# Voltage_60_Measure.net
KiCad netlist of a schematic drawn in Altium Designer
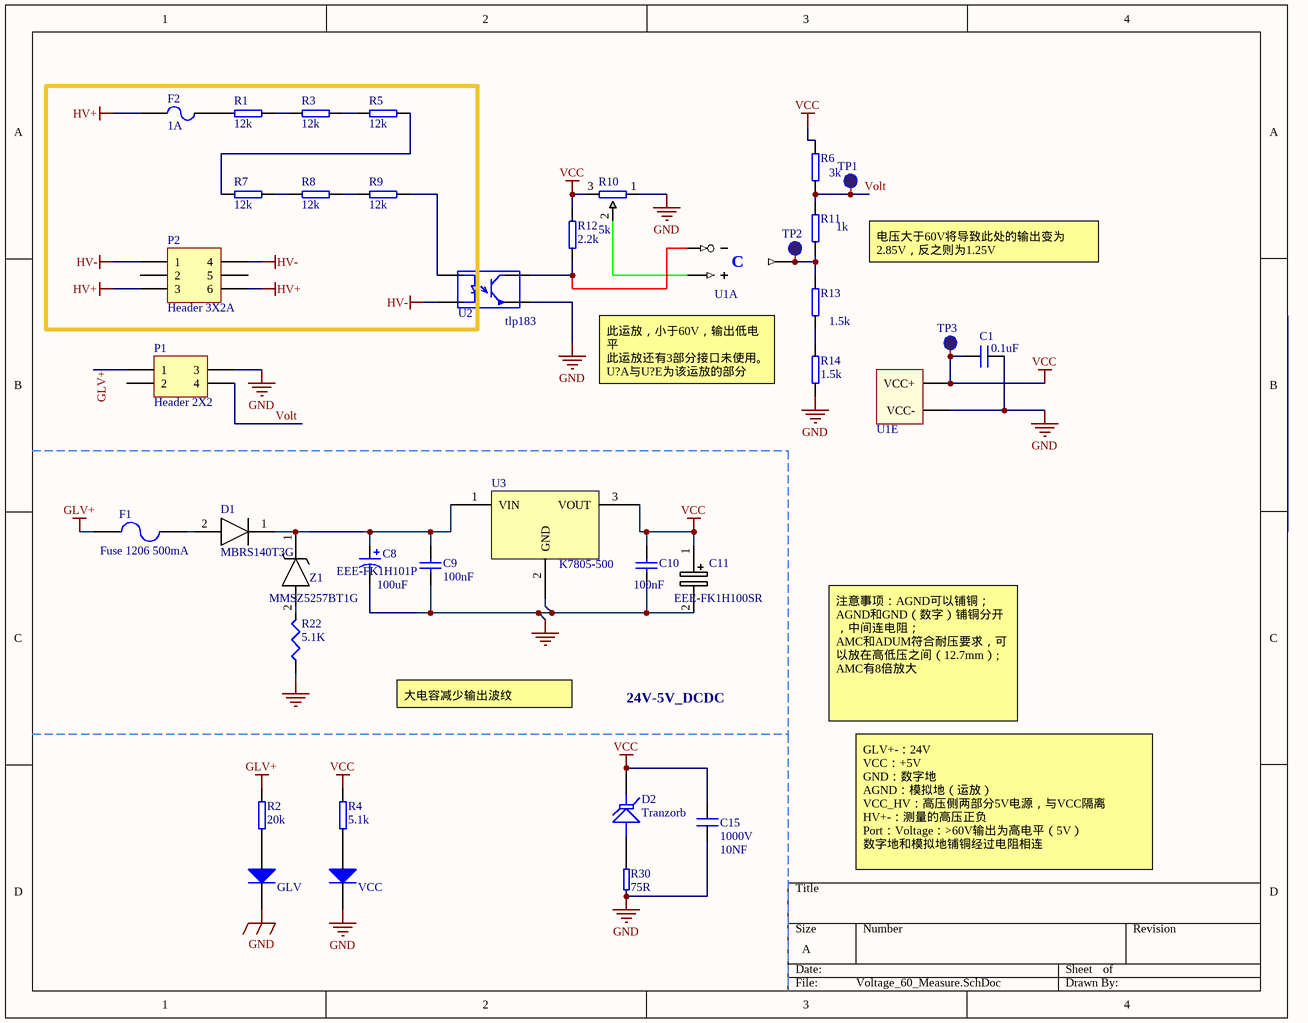
[diagram p0: Voltage_60_Measure.SchDoc]

(export (version "E")
  (design (tool "Eeschema 10.0.6"))
  (components
    (comp (ref "C1")
      (value "0.1uF")
      (footprint "C0603")
      (description "多层陶瓷电容器MLCC - SMD/SMT 0603 .1uF 50volts X7R 10%")
      (fields (field (name "MANUFACTURER") "Vishay") (field (name "VOLTAGE") "50V"))
      (libsource (lib "TSAL") (part "VJ0603Y104KXAAC"))
    )
    (comp (ref "C8")
      (value "EEE-FK1H101P")
      (footprint "C-RB-SD8")
      (description "Polarized Capacitor (Radial)")
      (fields (field (name "ALTIUM_VALUE") "100uF") (field (name "PUBLISHER") "Altium Limited"))
      (libsource (lib "Miscellaneous Devices") (part "Cap Pol1"))
    )
    (comp (ref "C9")
      (value "100nF")
      (footprint "C1206")
      (description "Capacitor (Semiconductor SIM Model)")
      (fields (field (name "Comment") "Cap Semi") (field (name "PUBLISHER") "Altium Limited"))
      (libsource (lib "Miscellaneous Devices") (part "Cap Semi"))
    )
    (comp (ref "C10")
      (value "100nF")
      (footprint "C1206")
      (description "Capacitor (Semiconductor SIM Model)")
      (fields (field (name "Comment") "Cap Semi") (field (name "PUBLISHER") "Altium Limited"))
      (libsource (lib "Miscellaneous Devices") (part "Cap Semi"))
    )
    (comp (ref "C11")
      (value "EEE-FK1H100SR")
      (footprint "CAPAE430X610N")
      (description "Capacitor Polarised")
      (fields (field (name "MOUSER PART NUMBER") "667-EEE-FK1H100SR"))
      (libsource (lib "*") (part "EEE-FK1H100SR"))
    )
    (comp (ref "C15")
      (value "10NF")
      (footprint "C1206")
      (description "多层陶瓷电容器MLCC - SMD/SMT 1206 1000pF 1KV C0G 5%")
      (fields
        (field (name "MANUFACTURER") "Vishay")
        (field (name "VOLTAGE") "1000V")
        (field (name "Comment") "VJ1206A102JXGAT5Z")
      )
      (libsource (lib "controller") (part "VJ1206A102JXGAT5Z"))
    )
    (comp (ref "D1")
      (value "MBRS140T3G")
      (footprint "DIOM5436X247N")
      (description "Diode")
      (fields (field (name "MOUSER PART NUMBER") "863-MBRS140T3G") (field (name "RS PART NUMBER") "5452074P"))
      (libsource (lib "*") (part "MBRS140T3G"))
    )
    (comp (ref "D2")
      (value "Tranzorb")
      (footprint "SOD123")
      (description "Transient Voltage Suppression (TVS) Diode")
      (fields (field (name "PUBLISHER") "Altium Limited"))
      (libsource (lib "Miscellaneous Devices") (part "Tranzorb"))
    )
    (comp (ref "F1")
      (value "Fuse 1206 500mA")
      (footprint "1206")
      (description "littelfuse 0437 .500")
      (fields (field (name "PUBLISHER") "Altium Limited"))
      (libsource (lib "Miscellaneous Devices") (part "Fuse 2"))
    )
    (comp (ref "F2")
      (value "1A")
      (footprint "0485500DR")
      (description "Fast-Acting 485 Series")
      (fields (field (name "MANUFACTURER") "Littefuse") (field (name "Comment") "0485500.DR"))
      (libsource (lib "TSAL") (part "0485500.DR"))
    )
    (comp (ref "GLV")
      (value "VLMB1310-GS08")
      (footprint "BlueLED 0603")
      (description "标准LED-SMD Blue Clear Non-Diff")
      (fields (field (name "MANUFACTURER") "Vishay"))
      (libsource (lib "BMU2019") (part "VLMB1310-GS08"))
    )
    (comp (ref "P1")
      (value "Header 2X2")
      (footprint "PHB2*2")
      (description "Header, 2-Pin, Dual row")
      (fields (field (name "PUBLISHER") "Altium Limited"))
      (libsource (lib "Miscellaneous Connectors") (part "Header 2X2"))
    )
    (comp (ref "P2")
      (value "Header 3X2A")
      (footprint "43045-0612")
      (description "Header, 3-Pin, Dual row")
      (fields (field (name "PUBLISHER") "Altium Limited"))
      (libsource (lib "Miscellaneous Connectors") (part "Header 3X2A"))
    )
    (comp (ref "R1")
      (value "12k")
      (footprint "R2512")
      (description "Thin Film Resistors - SMD 2.5watt 2Kohms .1% 25 PPM")
      (fields (field (name "MANUFACTURER") "Vishay") (field (name "VOLTAGE") "200V"))
      (libsource (lib "TSAL") (part "PHP02512E2001BST5"))
    )
    (comp (ref "R2")
      (value "20k")
      (footprint "R0603")
      (description "Thick Film Resistors - SMD 1/10Watt 20Kohms 1% Commercial Use")
      (fields (field (name "MANUFACTURER") "Vishay") (field (name "VOLTAGE") "75V"))
      (libsource (lib "BMU2019") (part "CRCW060320K0FKEAC"))
    )
    (comp (ref "R3")
      (value "12k")
      (footprint "R2512")
      (description "Thin Film Resistors - SMD 2.5watt 2Kohms .1% 25 PPM")
      (fields (field (name "MANUFACTURER") "Vishay") (field (name "VOLTAGE") "200V"))
      (libsource (lib "TSAL") (part "PHP02512E2001BST5"))
    )
    (comp (ref "R4")
      (value "5.1k")
      (footprint "R0603")
      (description "Thick Film Resistors - SMD 1/10Watt 5.1Kohms 1% Commercial Use")
      (fields (field (name "MANUFACTURER") "Vishay") (field (name "Comment") "CRCW06035K10JNEAC"))
      (libsource (lib "BMU2019") (part "CRCW06035K10JNEAC"))
    )
    (comp (ref "R5")
      (value "12k")
      (footprint "R2512")
      (description "Thin Film Resistors - SMD 2.5watt 2Kohms .1% 25 PPM")
      (fields (field (name "MANUFACTURER") "Vishay") (field (name "VOLTAGE") "200V"))
      (libsource (lib "TSAL") (part "PHP02512E2001BST5"))
    )
    (comp (ref "R6")
      (value "3k")
      (footprint "R0603")
      (description "Thick Film Resistors - SMD 1/10Watt 1.5Kohms 1% Commercial Use")
      (fields (field (name "MANUFACTURER") "Vishay") (field (name "Comment") "CRCW06031K50FKEAC"))
      (libsource (lib "BMU2019") (part "CRCW06031K50FKEAC"))
    )
    (comp (ref "R7")
      (value "12k")
      (footprint "R2512")
      (description "Thin Film Resistors - SMD 2.5watt 2Kohms .1% 25 PPM")
      (fields (field (name "MANUFACTURER") "Vishay") (field (name "VOLTAGE") "200V"))
      (libsource (lib "TSAL") (part "PHP02512E2001BST5"))
    )
    (comp (ref "R8")
      (value "12k")
      (footprint "R2512")
      (description "Thin Film Resistors - SMD 2.5watt 2Kohms .1% 25 PPM")
      (fields (field (name "MANUFACTURER") "Vishay") (field (name "VOLTAGE") "200V"))
      (libsource (lib "TSAL") (part "PHP02512E2001BST5"))
    )
    (comp (ref "R9")
      (value "12k")
      (footprint "R2512")
      (description "Thin Film Resistors - SMD 2.5watt 2Kohms .1% 25 PPM")
      (fields (field (name "MANUFACTURER") "Vishay") (field (name "VOLTAGE") "200V"))
      (libsource (lib "TSAL") (part "PHP02512E2001BST5"))
    )
    (comp (ref "R10")
      (value "5k")
      (footprint "3362p")
      (description "Trimmer Resistors - Through Hole 1/4\"SQ 5KOHMS 10% 0.5WATTS")
      (fields (field (name "MANUFACTURER") "Bourns") (field (name "Comment") "3362P-1-502LF"))
      (libsource (lib "TSAL") (part "3362P-1-502LF"))
    )
    (comp (ref "R11")
      (value "1k")
      (footprint "R0603")
      (description "Thick Film Resistors - SMD 1/10Watt 1Kohms 5% Commercial Use")
      (fields (field (name "MANUFACTURER") "Vishay") (field (name "VOLTAGE") "75V"))
      (libsource (lib "BMU2019") (part "CRCW06031K00JNEAC"))
    )
    (comp (ref "R12")
      (value "2.2k")
      (footprint "R0603")
      (description "Thick Film Resistors - SMD 1/10Watt 2.2Kohms 1% Commercial Use")
      (fields (field (name "MANUFACTURER") "Vishay") (field (name "VOLTAGE") "75V"))
      (libsource (lib "TSAL") (part "CRCW06032K20JNEAC"))
    )
    (comp (ref "R13")
      (value "1.5k")
      (footprint "R0603")
      (description "Thick Film Resistors - SMD 1/10Watt 1.5Kohms 1% Commercial Use")
      (fields (field (name "MANUFACTURER") "Vishay") (field (name "Comment") "CRCW06031K50FKEAC"))
      (libsource (lib "BMU2019") (part "CRCW06031K50FKEAC"))
    )
    (comp (ref "R14")
      (value "1.5k")
      (footprint "R0603")
      (description "Thick Film Resistors - SMD 1/10Watt 1Kohms 5% Commercial Use")
      (fields (field (name "MANUFACTURER") "Vishay") (field (name "VOLTAGE") "75V"))
      (libsource (lib "BMU2019") (part "CRCW06031K00JNEAC"))
    )
    (comp (ref "R22")
      (value "5.1K")
      (footprint "0805-2")
      (description "Resistor")
      (fields (field (name "Comment") "Res3") (field (name "PUBLISHER") "Altium Limited"))
      (libsource (lib "Miscellaneous Devices") (part "Res3"))
    )
    (comp (ref "R30")
      (value "75R")
      (footprint "R 0603")
      (fields (field (name "Comment") "R"))
      (libsource (lib "BMS") (part "R"))
    )
    (comp (ref "TP1") (value "TP") (footprint "TP") (libsource (lib "Testpoint") (part "TP")))
    (comp (ref "TP2") (value "TP") (footprint "TP") (libsource (lib "Testpoint") (part "TP")))
    (comp (ref "TP3") (value "TP") (footprint "TP") (libsource (lib "Testpoint") (part "TP")))
    (comp (ref "U1")
      (value "TSX3704IDT")
      (footprint "SO-14")
      (description "Analog Comparators Micropower (5uA) 16V quad CMOS comparator, push pull output")
      (fields (field (name "MANUFACTURER") "ST"))
      (libsource (lib "TSAL") (part "TSX3704IDT"))
    )
    (comp (ref "U2")
      (value "tlp183")
      (footprint "SOP-4")
      (description "Transistor Output Optocouplers 80V Vceo; 3750 Vrms SOP-4; 50-600 CTR")
      (libsource (lib "TSAL") (part "VOMA617A-X001T"))
    )
    (comp (ref "U3")
      (value "K7805-500")
      (footprint "K7805-500R3")
      (libsource (lib "BSPD_2019_V3") (part "K7805-500"))
    )
    (comp (ref "VCC")
      (value "VLMB1310-GS08")
      (footprint "BlueLED 0603")
      (description "标准LED-SMD Blue Clear Non-Diff")
      (fields (field (name "MANUFACTURER") "Vishay"))
      (libsource (lib "BMU2019") (part "VLMB1310-GS08"))
    )
    (comp (ref "Z1")
      (value "MMSZ5257BT1G")
      (footprint "SOD3716X135N")
      (description "Zener Diode")
      (fields
        (field (name "MOUSER PART NUMBER") "863-MMSZ5257BT1G")
        (field (name "RS PART NUMBER") "6547482")
      )
      (libsource (lib "*") (part "MMSZ5257BT1G"))
    )
  )
  (nets
    (net (code "1") (name "/Volt") (class "Default")
      (node (ref "P1") (pin "4") (pinfunction "4_4") (pintype "passive"))
      (node (ref "R11") (pin "2") (pinfunction "2_2") (pintype "passive"))
      (node (ref "R6") (pin "1") (pinfunction "1_1") (pintype "passive"))
      (node (ref "TP1") (pin "0") (pinfunction "0_0") (pintype "passive"))
    )
    (net (code "2") (name "GLV+") (class "Default")
      (node (ref "F1") (pin "1") (pinfunction "1_1") (pintype "passive"))
      (node (ref "P1") (pin "1") (pinfunction "1_1") (pintype "passive"))
      (node (ref "R2") (pin "2") (pinfunction "2_2") (pintype "passive"))
    )
    (net (code "3") (name "GND") (class "Default")
      (node (ref "C1") (pin "1") (pinfunction "1_1") (pintype "passive"))
      (node (ref "C10") (pin "1") (pinfunction "1_1") (pintype "passive"))
      (node (ref "C11") (pin "2") (pinfunction "-_2") (pintype "passive"))
      (node (ref "C15") (pin "2") (pinfunction "2_2") (pintype "passive"))
      (node (ref "C8") (pin "2") (pinfunction "2_2") (pintype "passive"))
      (node (ref "C9") (pin "1") (pinfunction "1_1") (pintype "passive"))
      (node (ref "GLV") (pin "C") (pinfunction "C_C") (pintype "passive"))
      (node (ref "P1") (pin "3") (pinfunction "3_3") (pintype "passive"))
      (node (ref "R10") (pin "1") (pinfunction "CCW_1") (pintype "passive"))
      (node (ref "R14") (pin "1") (pinfunction "1_1") (pintype "passive"))
      (node (ref "R22") (pin "1") (pinfunction "1_1") (pintype "passive"))
      (node (ref "R30") (pin "2") (pinfunction "2_2") (pintype "passive"))
      (node (ref "U1") (pin "12") (pinfunction "VCC-_12") (pintype "power_in"))
      (node (ref "U2") (pin "3") (pinfunction "E_3") (pintype "passive"))
      (node (ref "U3") (pin "2") (pinfunction "GND_2") (pintype "passive"))
      (node (ref "VCC") (pin "C") (pinfunction "C_C") (pintype "passive"))
    )
    (net (code "4") (name "HV+") (class "Default")
      (node (ref "F2") (pin "2") (pinfunction "2_2") (pintype "passive"))
      (node (ref "P2") (pin "3") (pinfunction "3_3") (pintype "passive"))
      (node (ref "P2") (pin "6") (pinfunction "6_6") (pintype "passive"))
    )
    (net (code "5") (name "HV-") (class "Default")
      (node (ref "P2") (pin "1") (pinfunction "1_1") (pintype "passive"))
      (node (ref "P2") (pin "4") (pinfunction "4_4") (pintype "passive"))
      (node (ref "U2") (pin "2") (pinfunction "C_2") (pintype "passive"))
    )
    (net (code "6") (name "Net-(D1-A)") (class "Default")
      (node (ref "D1") (pin "2") (pinfunction "A_2") (pintype "passive"))
      (node (ref "F1") (pin "2") (pinfunction "2_2") (pintype "passive"))
    )
    (net (code "7") (name "Net-(D1-K)") (class "Default")
      (node (ref "C8") (pin "1") (pinfunction "1_1") (pintype "passive"))
      (node (ref "C9") (pin "2") (pinfunction "2_2") (pintype "passive"))
      (node (ref "D1") (pin "1") (pinfunction "K_1") (pintype "passive"))
      (node (ref "U3") (pin "1") (pinfunction "VIN_1") (pintype "passive"))
      (node (ref "Z1") (pin "1") (pinfunction "K_1") (pintype "passive"))
    )
    (net (code "8") (name "Net-(D2-A)") (class "Default")
      (node (ref "D2") (pin "1") (pinfunction "A_1") (pintype "passive"))
      (node (ref "R30") (pin "1") (pinfunction "1_1") (pintype "passive"))
    )
    (net (code "9") (name "Net-(F2-Pad1)") (class "Default")
      (node (ref "F2") (pin "1") (pinfunction "1_1") (pintype "passive"))
      (node (ref "R1") (pin "2") (pinfunction "2_2") (pintype "passive"))
    )
    (net (code "10") (name "Net-(GLV-PadA)") (class "Default")
      (node (ref "GLV") (pin "A") (pinfunction "A_A") (pintype "passive"))
      (node (ref "R2") (pin "1") (pinfunction "1_1") (pintype "passive"))
    )
    (net (code "11") (name "Net-(R1-Pad1)") (class "Default")
      (node (ref "R1") (pin "1") (pinfunction "1_1") (pintype "passive"))
      (node (ref "R3") (pin "2") (pinfunction "2_2") (pintype "passive"))
    )
    (net (code "12") (name "Net-(R3-Pad1)") (class "Default")
      (node (ref "R3") (pin "1") (pinfunction "1_1") (pintype "passive"))
      (node (ref "R5") (pin "2") (pinfunction "2_2") (pintype "passive"))
    )
    (net (code "13") (name "Net-(R4-Pad1)") (class "Default")
      (node (ref "R4") (pin "1") (pinfunction "1_1") (pintype "passive"))
      (node (ref "VCC") (pin "A") (pinfunction "A_A") (pintype "passive"))
    )
    (net (code "14") (name "Net-(R5-Pad1)") (class "Default")
      (node (ref "R5") (pin "1") (pinfunction "1_1") (pintype "passive"))
      (node (ref "R7") (pin "2") (pinfunction "2_2") (pintype "passive"))
    )
    (net (code "15") (name "Net-(R7-Pad1)") (class "Default")
      (node (ref "R7") (pin "1") (pinfunction "1_1") (pintype "passive"))
      (node (ref "R8") (pin "2") (pinfunction "2_2") (pintype "passive"))
    )
    (net (code "16") (name "Net-(R8-Pad1)") (class "Default")
      (node (ref "R8") (pin "1") (pinfunction "1_1") (pintype "passive"))
      (node (ref "R9") (pin "2") (pinfunction "2_2") (pintype "passive"))
    )
    (net (code "17") (name "Net-(R10-WIPER)") (class "Default")
      (node (ref "R10") (pin "2") (pinfunction "WIPER_2") (pintype "passive"))
      (node (ref "U1") (pin "5") (pinfunction "IN+_5") (pintype "input"))
    )
    (net (code "18") (name "Net-(R13-Pad1)") (class "Default")
      (node (ref "R13") (pin "1") (pinfunction "1_1") (pintype "passive"))
      (node (ref "R14") (pin "2") (pinfunction "2_2") (pintype "passive"))
    )
    (net (code "19") (name "Net-(U1A-IN-)") (class "Default")
      (node (ref "R12") (pin "1") (pinfunction "1_1") (pintype "passive"))
      (node (ref "U1") (pin "4") (pinfunction "IN-_4") (pintype "input"))
      (node (ref "U2") (pin "4") (pinfunction "C_4") (pintype "passive"))
    )
    (net (code "20") (name "Net-(U1A-OUT)") (class "Default")
      (node (ref "R11") (pin "1") (pinfunction "1_1") (pintype "passive"))
      (node (ref "R13") (pin "2") (pinfunction "2_2") (pintype "passive"))
      (node (ref "TP2") (pin "0") (pinfunction "0_0") (pintype "passive"))
      (node (ref "U1") (pin "2") (pinfunction "OUT_2") (pintype "output"))
    )
    (net (code "21") (name "Net-(U2-A)") (class "Default")
      (node (ref "R9") (pin "1") (pinfunction "1_1") (pintype "passive"))
      (node (ref "U2") (pin "1") (pinfunction "A_1") (pintype "passive"))
    )
    (net (code "22") (name "Net-(Z1-A)") (class "Default")
      (node (ref "R22") (pin "2") (pinfunction "2_2") (pintype "passive"))
      (node (ref "Z1") (pin "2") (pinfunction "A_2") (pintype "passive"))
    )
    (net (code "23") (name "VCC") (class "Default")
      (node (ref "C1") (pin "2") (pinfunction "2_2") (pintype "passive"))
      (node (ref "C10") (pin "2") (pinfunction "2_2") (pintype "passive"))
      (node (ref "C11") (pin "1") (pinfunction "+_1") (pintype "passive"))
      (node (ref "C15") (pin "1") (pinfunction "1_1") (pintype "passive"))
      (node (ref "D2") (pin "2") (pinfunction "K_2") (pintype "passive"))
      (node (ref "R10") (pin "3") (pinfunction "CW_3") (pintype "passive"))
      (node (ref "R12") (pin "2") (pinfunction "2_2") (pintype "passive"))
      (node (ref "R4") (pin "2") (pinfunction "2_2") (pintype "passive"))
      (node (ref "R6") (pin "2") (pinfunction "2_2") (pintype "passive"))
      (node (ref "TP3") (pin "0") (pinfunction "0_0") (pintype "passive"))
      (node (ref "U1") (pin "3") (pinfunction "VCC+_3") (pintype "power_in"))
      (node (ref "U3") (pin "3") (pinfunction "VOUT_3") (pintype "passive"))
    )
    (net (code "24") (name "unconnected-(P1-Pad2)") (class "Default")
      (node (ref "P1") (pin "2") (pinfunction "2_2") (pintype "passive"))
    )
    (net (code "25") (name "unconnected-(P2-Pad2)") (class "Default")
      (node (ref "P2") (pin "2") (pinfunction "2_2") (pintype "passive"))
    )
    (net (code "26") (name "unconnected-(P2-Pad5)") (class "Default")
      (node (ref "P2") (pin "5") (pinfunction "5_5") (pintype "passive"))
    )
  )
)
